# strip.net
KiCad netlist of a schematic drawn in EAGLE
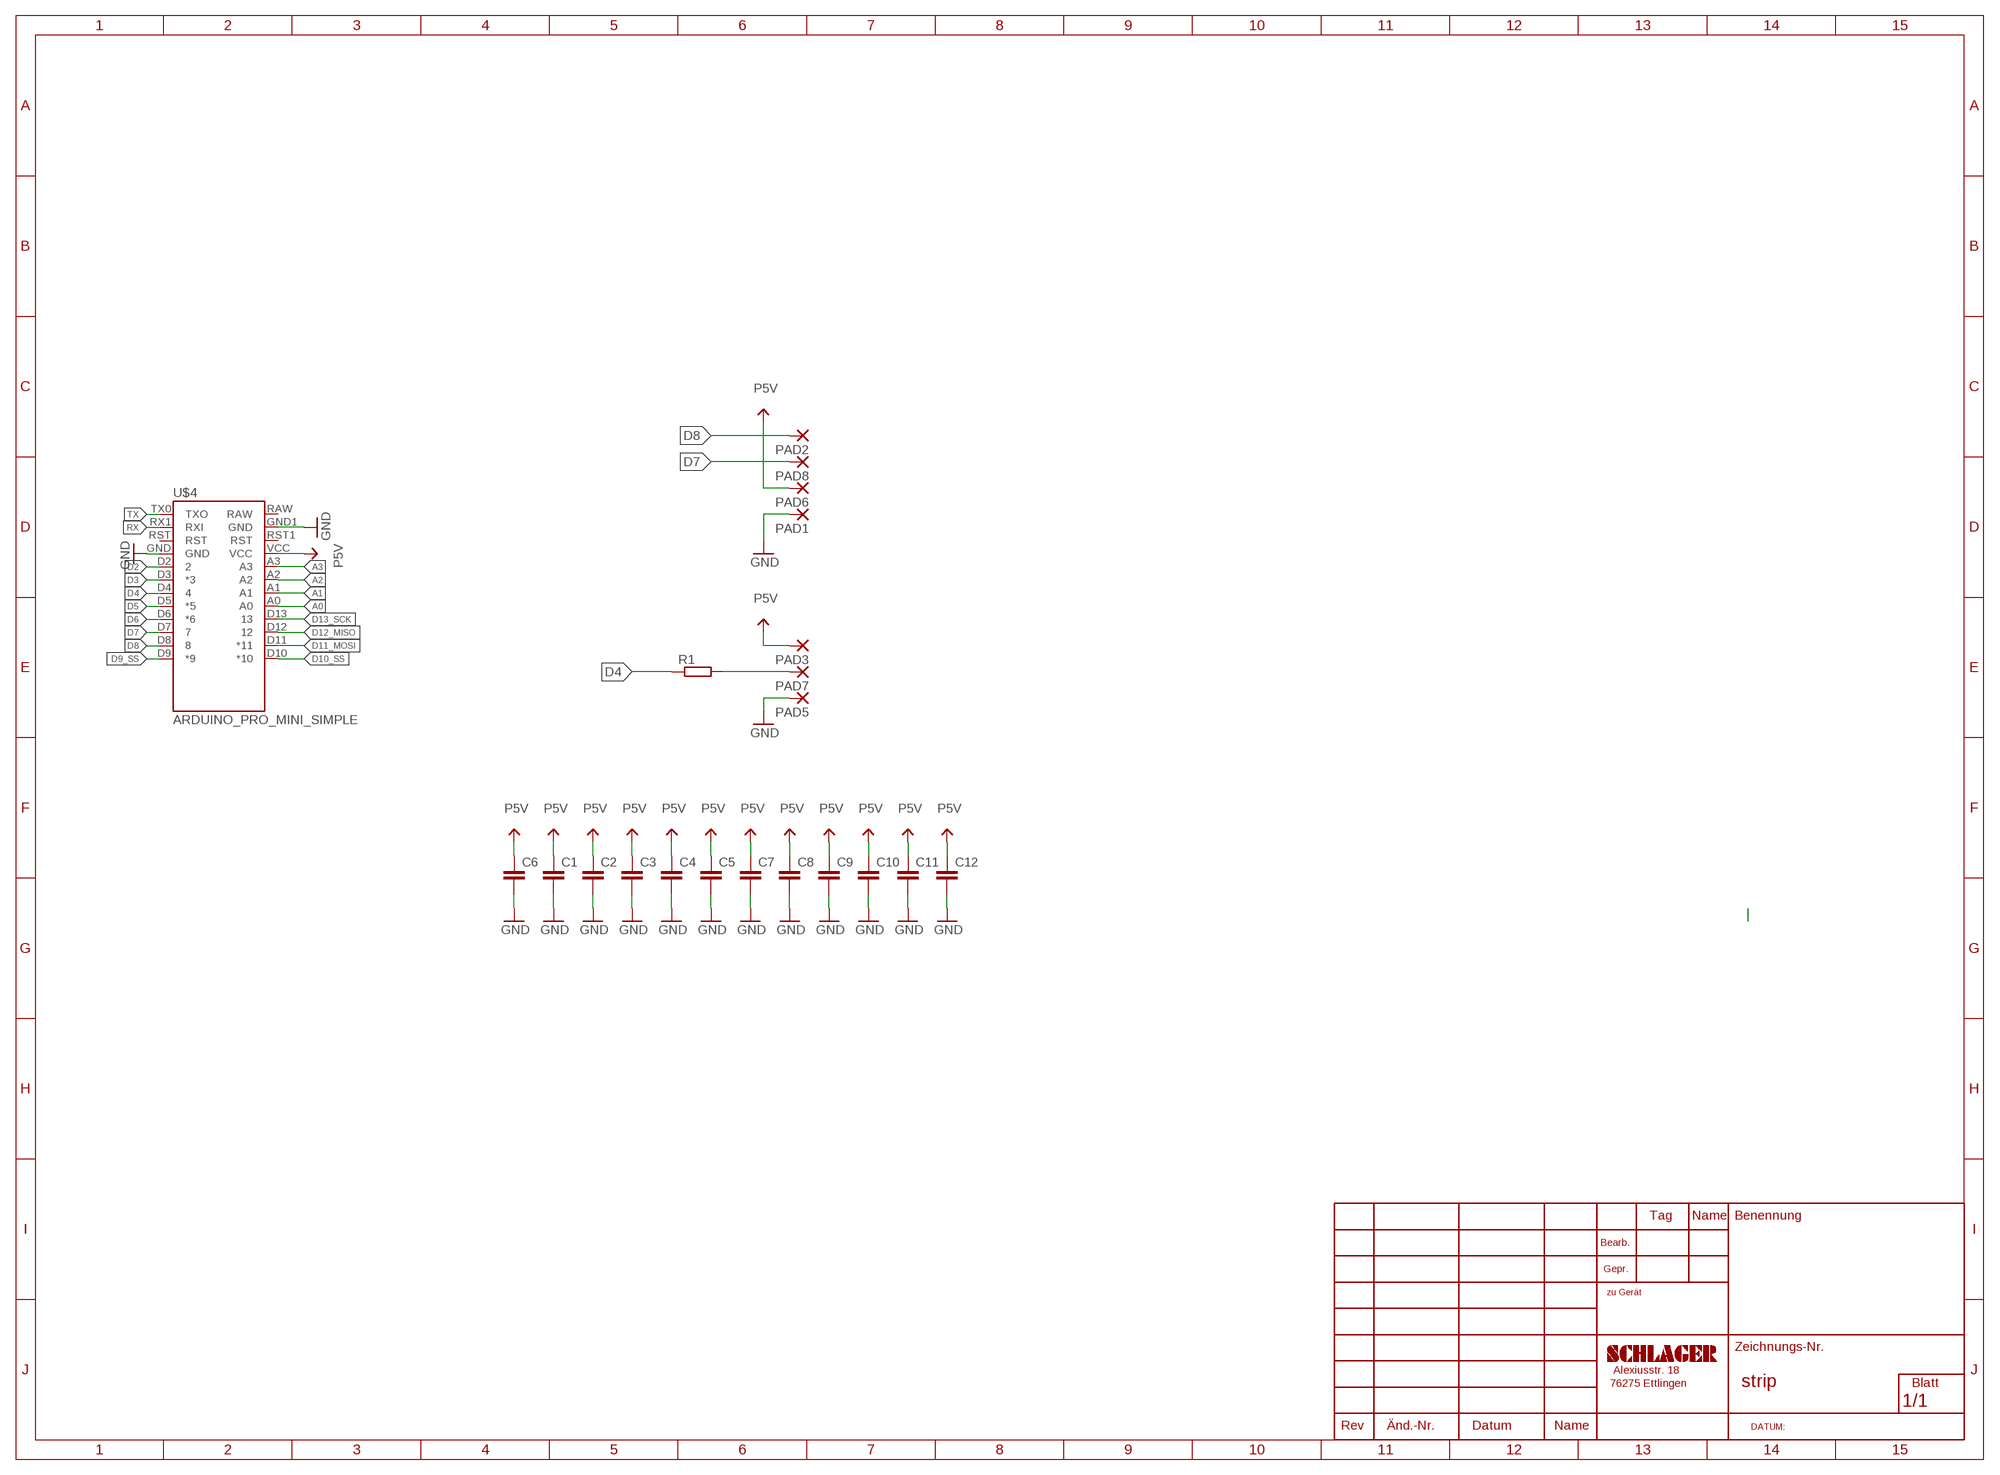
[diagram p0: schematic, sheet 1]

(export (version "E")
  (design (tool "Eeschema 10.0.6"))
  (components
    (comp (ref "C1")
      (value "C-EUC1210K")
      (footprint "eagle-import:C1210K")
      (libsource (lib "eagle-import") (part "C-EUC1210K"))
    )
    (comp (ref "C2")
      (value "C-EUC1210K")
      (footprint "eagle-import:C1210K")
      (libsource (lib "eagle-import") (part "C-EUC1210K"))
    )
    (comp (ref "C3")
      (value "C-EUC1210K")
      (footprint "eagle-import:C1210K")
      (libsource (lib "eagle-import") (part "C-EUC1210K"))
    )
    (comp (ref "C4")
      (value "C-EUC1210K")
      (footprint "eagle-import:C1210K")
      (libsource (lib "eagle-import") (part "C-EUC1210K"))
    )
    (comp (ref "C5")
      (value "C-EUC1210K")
      (footprint "eagle-import:C1210K")
      (libsource (lib "eagle-import") (part "C-EUC1210K"))
    )
    (comp (ref "C6")
      (value "C-EUC1210K")
      (footprint "eagle-import:C1210K")
      (libsource (lib "eagle-import") (part "C-EUC1210K"))
    )
    (comp (ref "C7")
      (value "C-EUC1206K")
      (footprint "eagle-import:C1206K")
      (libsource (lib "eagle-import") (part "C-EUC1206K"))
    )
    (comp (ref "C8")
      (value "C-EUC1206K")
      (footprint "eagle-import:C1206K")
      (libsource (lib "eagle-import") (part "C-EUC1206K"))
    )
    (comp (ref "C9")
      (value "C-EUC1206K")
      (footprint "eagle-import:C1206K")
      (libsource (lib "eagle-import") (part "C-EUC1206K"))
    )
    (comp (ref "C10")
      (value "C-EUC1206K")
      (footprint "eagle-import:C1206K")
      (libsource (lib "eagle-import") (part "C-EUC1206K"))
    )
    (comp (ref "C11")
      (value "C-EUC1206K")
      (footprint "eagle-import:C1206K")
      (libsource (lib "eagle-import") (part "C-EUC1206K"))
    )
    (comp (ref "C12")
      (value "C-EUC1206K")
      (footprint "eagle-import:C1206K")
      (libsource (lib "eagle-import") (part "C-EUC1206K"))
    )
    (comp (ref "PAD1")
      (value "SMD2")
      (footprint "eagle-import:SMD1,27-2,54")
      (libsource (lib "eagle-import") (part "SMD2"))
    )
    (comp (ref "PAD2")
      (value "SMD2")
      (footprint "eagle-import:SMD1,27-2,54")
      (libsource (lib "eagle-import") (part "SMD2"))
    )
    (comp (ref "PAD3")
      (value "SMD2")
      (footprint "eagle-import:SMD1,27-2,54")
      (libsource (lib "eagle-import") (part "SMD2"))
    )
    (comp (ref "PAD5")
      (value "SMD2")
      (footprint "eagle-import:SMD1,27-2,54")
      (libsource (lib "eagle-import") (part "SMD2"))
    )
    (comp (ref "PAD6")
      (value "SMD2")
      (footprint "eagle-import:SMD1,27-2,54")
      (libsource (lib "eagle-import") (part "SMD2"))
    )
    (comp (ref "PAD7")
      (value "SMD2")
      (footprint "eagle-import:SMD1,27-2,54")
      (libsource (lib "eagle-import") (part "SMD2"))
    )
    (comp (ref "PAD8")
      (value "SMD2")
      (footprint "eagle-import:SMD1,27-2,54")
      (libsource (lib "eagle-import") (part "SMD2"))
    )
    (comp (ref "R1")
      (value "R-EU_R0805")
      (footprint "eagle-import:R0805")
      (libsource (lib "eagle-import") (part "R-EU_R0805"))
    )
    (comp (ref "U$4")
      (value "ARDUINO_PRO_MINI_SIMPLE")
      (footprint "eagle-import:PRO_MINI_SIMPLE")
      (libsource (lib "eagle-import") (part "ARDUINO_PRO_MINI_SIMPLE"))
    )
  )
  (nets
    (net (code "1") (name "A0") (class "Default")
      (node (ref "U$4") (pin "A0") (pinfunction "A0_A0") (pintype "bidirectional"))
    )
    (net (code "2") (name "A1") (class "Default")
      (node (ref "U$4") (pin "A1") (pinfunction "A1_A1") (pintype "bidirectional"))
    )
    (net (code "3") (name "A2") (class "Default")
      (node (ref "U$4") (pin "A2") (pinfunction "A2_A2") (pintype "bidirectional"))
    )
    (net (code "4") (name "A3") (class "Default")
      (node (ref "U$4") (pin "A3") (pinfunction "A3_A3") (pintype "bidirectional"))
    )
    (net (code "5") (name "D2") (class "Default")
      (node (ref "U$4") (pin "D2") (pinfunction "2_D2") (pintype "bidirectional"))
    )
    (net (code "6") (name "D3") (class "Default")
      (node (ref "U$4") (pin "D3") (pinfunction "*3_D3") (pintype "bidirectional"))
    )
    (net (code "7") (name "D4") (class "Default")
      (node (ref "R1") (pin "1") (pinfunction "1_1") (pintype "passive"))
      (node (ref "U$4") (pin "D4") (pinfunction "4_D4") (pintype "bidirectional"))
    )
    (net (code "8") (name "D5") (class "Default")
      (node (ref "U$4") (pin "D5") (pinfunction "*5_D5") (pintype "bidirectional"))
    )
    (net (code "9") (name "D6") (class "Default")
      (node (ref "U$4") (pin "D6") (pinfunction "*6_D6") (pintype "bidirectional"))
    )
    (net (code "10") (name "D7") (class "Default")
      (node (ref "PAD8") (pin "1") (pinfunction "P_1") (pintype "passive"))
      (node (ref "U$4") (pin "D7") (pinfunction "7_D7") (pintype "bidirectional"))
    )
    (net (code "11") (name "D8") (class "Default")
      (node (ref "PAD2") (pin "1") (pinfunction "P_1") (pintype "passive"))
      (node (ref "U$4") (pin "D8") (pinfunction "8_D8") (pintype "bidirectional"))
    )
    (net (code "12") (name "D9_SS") (class "Default")
      (node (ref "U$4") (pin "D9") (pinfunction "*9_D9") (pintype "bidirectional"))
    )
    (net (code "13") (name "D10_SS") (class "Default")
      (node (ref "U$4") (pin "D10") (pinfunction "*10_D10") (pintype "bidirectional"))
    )
    (net (code "14") (name "D11_MOSI") (class "Default")
      (node (ref "U$4") (pin "D11") (pinfunction "*11_D11") (pintype "bidirectional"))
    )
    (net (code "15") (name "D12_MISO") (class "Default")
      (node (ref "U$4") (pin "D12") (pinfunction "12_D12") (pintype "bidirectional"))
    )
    (net (code "16") (name "D13_SCK") (class "Default")
      (node (ref "U$4") (pin "D13") (pinfunction "13_D13") (pintype "bidirectional"))
    )
    (net (code "17") (name "GND") (class "Default")
      (node (ref "C1") (pin "2") (pinfunction "2_2") (pintype "passive"))
      (node (ref "C10") (pin "2") (pinfunction "2_2") (pintype "passive"))
      (node (ref "C11") (pin "2") (pinfunction "2_2") (pintype "passive"))
      (node (ref "C12") (pin "2") (pinfunction "2_2") (pintype "passive"))
      (node (ref "C2") (pin "2") (pinfunction "2_2") (pintype "passive"))
      (node (ref "C3") (pin "2") (pinfunction "2_2") (pintype "passive"))
      (node (ref "C4") (pin "2") (pinfunction "2_2") (pintype "passive"))
      (node (ref "C5") (pin "2") (pinfunction "2_2") (pintype "passive"))
      (node (ref "C6") (pin "2") (pinfunction "2_2") (pintype "passive"))
      (node (ref "C7") (pin "2") (pinfunction "2_2") (pintype "passive"))
      (node (ref "C8") (pin "2") (pinfunction "2_2") (pintype "passive"))
      (node (ref "C9") (pin "2") (pinfunction "2_2") (pintype "passive"))
      (node (ref "PAD1") (pin "1") (pinfunction "P_1") (pintype "passive"))
      (node (ref "PAD5") (pin "1") (pinfunction "P_1") (pintype "passive"))
      (node (ref "U$4") (pin "GND") (pinfunction "GND_GND") (pintype "bidirectional"))
      (node (ref "U$4") (pin "GND1") (pinfunction "GND_GND1") (pintype "bidirectional"))
    )
    (net (code "18") (name "Net-(PAD7-P)") (class "Default")
      (node (ref "PAD7") (pin "1") (pinfunction "P_1") (pintype "passive"))
      (node (ref "R1") (pin "2") (pinfunction "2_2") (pintype "passive"))
    )
    (net (code "19") (name "P5V") (class "Default")
      (node (ref "C1") (pin "1") (pinfunction "1_1") (pintype "passive"))
      (node (ref "C10") (pin "1") (pinfunction "1_1") (pintype "passive"))
      (node (ref "C11") (pin "1") (pinfunction "1_1") (pintype "passive"))
      (node (ref "C12") (pin "1") (pinfunction "1_1") (pintype "passive"))
      (node (ref "C2") (pin "1") (pinfunction "1_1") (pintype "passive"))
      (node (ref "C3") (pin "1") (pinfunction "1_1") (pintype "passive"))
      (node (ref "C4") (pin "1") (pinfunction "1_1") (pintype "passive"))
      (node (ref "C5") (pin "1") (pinfunction "1_1") (pintype "passive"))
      (node (ref "C6") (pin "1") (pinfunction "1_1") (pintype "passive"))
      (node (ref "C7") (pin "1") (pinfunction "1_1") (pintype "passive"))
      (node (ref "C8") (pin "1") (pinfunction "1_1") (pintype "passive"))
      (node (ref "C9") (pin "1") (pinfunction "1_1") (pintype "passive"))
      (node (ref "PAD3") (pin "1") (pinfunction "P_1") (pintype "passive"))
      (node (ref "PAD6") (pin "1") (pinfunction "P_1") (pintype "passive"))
      (node (ref "U$4") (pin "VCC") (pinfunction "VCC_VCC") (pintype "bidirectional"))
    )
    (net (code "20") (name "RX") (class "Default")
      (node (ref "U$4") (pin "RX1") (pinfunction "RXI_RX1") (pintype "bidirectional"))
    )
    (net (code "21") (name "TX") (class "Default")
      (node (ref "U$4") (pin "TX0") (pinfunction "TXO_TX0") (pintype "bidirectional"))
    )
    (net (code "22") (name "unconnected-(U$4-PadRAW)") (class "Default")
      (node (ref "U$4") (pin "RAW") (pinfunction "RAW_RAW") (pintype "bidirectional"))
    )
    (net (code "23") (name "unconnected-(U$4-PadRST)") (class "Default")
      (node (ref "U$4") (pin "RST") (pinfunction "RST_RST") (pintype "bidirectional"))
    )
    (net (code "24") (name "unconnected-(U$4-RST-PadRST1)") (class "Default")
      (node (ref "U$4") (pin "RST1") (pinfunction "RST_RST1") (pintype "bidirectional"))
    )
  )
)
